# Sheet1.net
KiCad netlist of a schematic drawn in Altium Designer
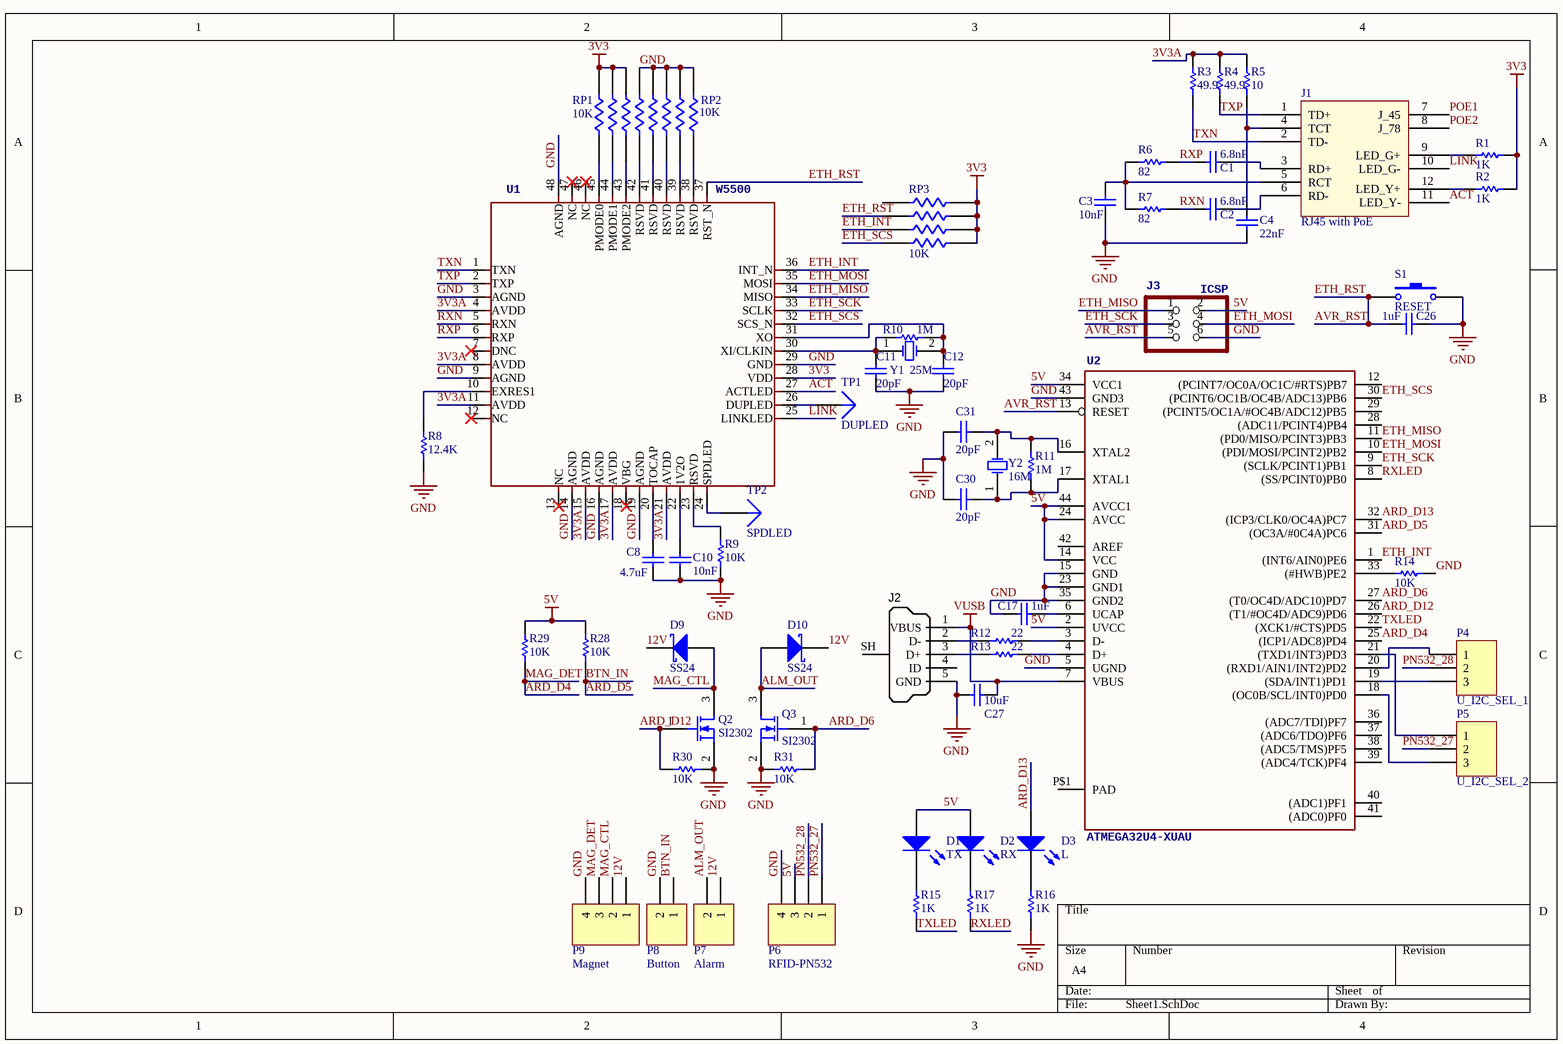
[diagram p0: Sheet1.SchDoc]

(export (version "E")
  (design (tool "Eeschema 10.0.6"))
  (components
    (comp (ref "C1")
      (value "6.8nF")
      (footprint "C-1608[0603]")
      (description "Capacitor (Semiconductor SIM Model)")
      (fields (field (name "Comment") "Cap Semi") (field (name "PUBLISHER") "Altium Limited"))
      (libsource (lib "Miscellaneous Devices") (part "Cap Semi"))
    )
    (comp (ref "C2")
      (value "6.8nF")
      (footprint "C-1608[0603]")
      (description "Capacitor (Semiconductor SIM Model)")
      (fields (field (name "Comment") "Cap Semi") (field (name "PUBLISHER") "Altium Limited"))
      (libsource (lib "Miscellaneous Devices") (part "Cap Semi"))
    )
    (comp (ref "C3")
      (value "10nF")
      (footprint "C-1608[0603]")
      (description "Capacitor (Semiconductor SIM Model)")
      (fields (field (name "Comment") "Cap Semi") (field (name "PUBLISHER") "Altium Limited"))
      (libsource (lib "Miscellaneous Devices") (part "Cap Semi"))
    )
    (comp (ref "C4")
      (value "22nF")
      (footprint "C-1608[0603]")
      (description "Capacitor (Semiconductor SIM Model)")
      (fields (field (name "Comment") "Cap Semi") (field (name "PUBLISHER") "Altium Limited"))
      (libsource (lib "Miscellaneous Devices") (part "Cap Semi"))
    )
    (comp (ref "C8")
      (value "4.7uF")
      (footprint "C-1608[0603]")
      (description "Capacitor (Semiconductor SIM Model)")
      (fields (field (name "Comment") "Cap Semi") (field (name "PUBLISHER") "Altium Limited"))
      (libsource (lib "Miscellaneous Devices") (part "Cap Semi"))
    )
    (comp (ref "C10")
      (value "10nF")
      (footprint "C-1608[0603]")
      (description "Capacitor (Semiconductor SIM Model)")
      (fields (field (name "Comment") "Cap Semi") (field (name "PUBLISHER") "Altium Limited"))
      (libsource (lib "Miscellaneous Devices") (part "Cap Semi"))
    )
    (comp (ref "C11")
      (value "20pF")
      (footprint "C-1608[0603]")
      (description "Capacitor (Semiconductor SIM Model)")
      (fields (field (name "Comment") "Cap Semi") (field (name "PUBLISHER") "Altium Limited"))
      (libsource (lib "Miscellaneous Devices") (part "Cap Semi"))
    )
    (comp (ref "C12")
      (value "20pF")
      (footprint "C-1608[0603]")
      (description "Capacitor (Semiconductor SIM Model)")
      (fields (field (name "Comment") "Cap Semi") (field (name "PUBLISHER") "Altium Limited"))
      (libsource (lib "Miscellaneous Devices") (part "Cap Semi"))
    )
    (comp (ref "C17")
      (value "1uF")
      (footprint "C-1608[0603]")
      (description "Capacitor (Semiconductor SIM Model)")
      (fields (field (name "Comment") "Cap Semi") (field (name "PUBLISHER") "Altium Limited"))
      (libsource (lib "Miscellaneous Devices") (part "Cap Semi"))
    )
    (comp (ref "C26")
      (value "1uF")
      (footprint "C-1608[0603]")
      (description "Capacitor (Semiconductor SIM Model)")
      (fields (field (name "Comment") "Cap Semi") (field (name "PUBLISHER") "Altium Limited"))
      (libsource (lib "Miscellaneous Devices") (part "Cap Semi"))
    )
    (comp (ref "C27")
      (value "10uF")
      (footprint "C-1608[0603]")
      (description "Capacitor (Semiconductor SIM Model)")
      (fields (field (name "Comment") "Cap Semi") (field (name "PUBLISHER") "Altium Limited"))
      (libsource (lib "Miscellaneous Devices") (part "Cap Semi"))
    )
    (comp (ref "C30")
      (value "20pF")
      (footprint "C-1608[0603]")
      (description "Capacitor (Semiconductor SIM Model)")
      (fields (field (name "Comment") "Cap Semi") (field (name "PUBLISHER") "Altium Limited"))
      (libsource (lib "Miscellaneous Devices") (part "Cap Semi"))
    )
    (comp (ref "C31")
      (value "20pF")
      (footprint "C-1608[0603]")
      (description "Capacitor (Semiconductor SIM Model)")
      (fields (field (name "Comment") "Cap Semi") (field (name "PUBLISHER") "Altium Limited"))
      (libsource (lib "Miscellaneous Devices") (part "Cap Semi"))
    )
    (comp (ref "D1")
      (value "TX")
      (footprint "LED-1608[0603]-R")
      (description "Typical RED GaAs LED")
      (fields (field (name "PUBLISHER") "Altium Limited"))
      (libsource (lib "Miscellaneous Devices") (part "LED1"))
    )
    (comp (ref "D2")
      (value "RX")
      (footprint "LED-1608[0603]-R")
      (description "Typical RED GaAs LED")
      (fields (field (name "PUBLISHER") "Altium Limited"))
      (libsource (lib "Miscellaneous Devices") (part "LED1"))
    )
    (comp (ref "D3")
      (value "L")
      (footprint "LED-1608[0603]-R")
      (description "Typical RED GaAs LED")
      (fields (field (name "PUBLISHER") "Altium Limited"))
      (libsource (lib "Miscellaneous Devices") (part "LED1"))
    )
    (comp (ref "D9")
      (value "SS24")
      (footprint "DO-214AC")
      (description "Schottky Diode")
      (fields (field (name "PUBLISHER") "Altium Limited"))
      (libsource (lib "Miscellaneous Devices") (part "D Schottky"))
    )
    (comp (ref "D10")
      (value "SS24")
      (footprint "DO-214AC")
      (description "Schottky Diode")
      (fields (field (name "PUBLISHER") "Altium Limited"))
      (libsource (lib "Miscellaneous Devices") (part "D Schottky"))
    )
    (comp (ref "J1")
      (value "RJ45 with PoE")
      (footprint "HR911105A")
      (libsource (lib "Schlib1") (part "HLJ-6115ANL"))
    )
    (comp (ref "J2")
      (value "USB Micro Type B")
      (footprint "MICRO USB 3D")
      (description "Connector SMD USB Micro Type B middle mount")
      (libsource (lib "Schlib1") (part "USB_Micro_TypeB"))
    )
    (comp (ref "J3") (value "ICSP") (footprint "HDR2X3") (libsource (lib "SmartPrj") (part "PINHD-2X3")))
    (comp (ref "P4")
      (value "U_I2C_SEL_1")
      (footprint "shortPad")
      (description "Header, 3-Pin")
      (fields (field (name "PUBLISHER") "Altium Limited"))
      (libsource (lib "Miscellaneous Connectors") (part "Header 3"))
    )
    (comp (ref "P5")
      (value "U_I2C_SEL_2")
      (footprint "shortPad")
      (description "Header, 3-Pin")
      (fields (field (name "PUBLISHER") "Altium Limited"))
      (libsource (lib "Miscellaneous Connectors") (part "Header 3"))
    )
    (comp (ref "P6")
      (value "RFID-PN532")
      (footprint "HDR1X4H")
      (description "Header, 4-Pin, Right Angle")
      (fields (field (name "PUBLISHER") "Altium Limited"))
      (libsource (lib "Miscellaneous Connectors") (part "Header 4H"))
    )
    (comp (ref "P7")
      (value "Alarm")
      (footprint "HDR1X2H")
      (description "Header, 2-Pin, Right Angle")
      (fields (field (name "PUBLISHER") "Altium Limited"))
      (libsource (lib "Miscellaneous Connectors") (part "Header 2H"))
    )
    (comp (ref "P8")
      (value "Button")
      (footprint "HDR1X2H")
      (description "Header, 2-Pin, Right Angle")
      (fields (field (name "PUBLISHER") "Altium Limited"))
      (libsource (lib "Miscellaneous Connectors") (part "Header 2H"))
    )
    (comp (ref "P9")
      (value "Magnet")
      (footprint "HDR1X4H")
      (description "Header, 4-Pin, Right Angle")
      (fields (field (name "PUBLISHER") "Altium Limited"))
      (libsource (lib "Miscellaneous Connectors") (part "Header 4H"))
    )
    (comp (ref "Q2")
      (value "SI2302")
      (footprint "SOT23B")
      (description "N-Channel MOSFET")
      (fields (field (name "PUBLISHER") "Altium Limited"))
      (libsource (lib "Schlib1") (part "SI2302"))
    )
    (comp (ref "Q3")
      (value "SI2302")
      (footprint "SOT23B")
      (description "N-Channel MOSFET")
      (fields (field (name "PUBLISHER") "Altium Limited"))
      (libsource (lib "Schlib1") (part "SI2302"))
    )
    (comp (ref "R1")
      (value "1K")
      (footprint "R-1608[0603]")
      (description "Semiconductor Resistor")
      (fields (field (name "Comment") "Res Semi") (field (name "PUBLISHER") "Altium Limited"))
      (libsource (lib "Miscellaneous Devices") (part "Res Semi"))
    )
    (comp (ref "R2")
      (value "1K")
      (footprint "R-1608[0603]")
      (description "Semiconductor Resistor")
      (fields (field (name "Comment") "Res Semi") (field (name "PUBLISHER") "Altium Limited"))
      (libsource (lib "Miscellaneous Devices") (part "Res Semi"))
    )
    (comp (ref "R3")
      (value "49.9")
      (footprint "R-1608[0603]")
      (description "Semiconductor Resistor")
      (fields (field (name "Comment") "Res Semi") (field (name "PUBLISHER") "Altium Limited"))
      (libsource (lib "Miscellaneous Devices") (part "Res Semi"))
    )
    (comp (ref "R4")
      (value "49.9")
      (footprint "R-1608[0603]")
      (description "Semiconductor Resistor")
      (fields (field (name "Comment") "Res Semi") (field (name "PUBLISHER") "Altium Limited"))
      (libsource (lib "Miscellaneous Devices") (part "Res Semi"))
    )
    (comp (ref "R5")
      (value "10")
      (footprint "R-1608[0603]")
      (description "Semiconductor Resistor")
      (fields (field (name "Comment") "Res Semi") (field (name "PUBLISHER") "Altium Limited"))
      (libsource (lib "Miscellaneous Devices") (part "Res Semi"))
    )
    (comp (ref "R6")
      (value "82")
      (footprint "R-1608[0603]")
      (description "Semiconductor Resistor")
      (fields (field (name "Comment") "Res Semi") (field (name "PUBLISHER") "Altium Limited"))
      (libsource (lib "Miscellaneous Devices") (part "Res Semi"))
    )
    (comp (ref "R7")
      (value "82")
      (footprint "R-1608[0603]")
      (description "Semiconductor Resistor")
      (fields (field (name "Comment") "Res Semi") (field (name "PUBLISHER") "Altium Limited"))
      (libsource (lib "Miscellaneous Devices") (part "Res Semi"))
    )
    (comp (ref "R8")
      (value "12.4K")
      (footprint "R-1608[0603]")
      (description "Semiconductor Resistor")
      (fields (field (name "Comment") "Res Semi") (field (name "PUBLISHER") "Altium Limited"))
      (libsource (lib "Miscellaneous Devices") (part "Res Semi"))
    )
    (comp (ref "R9")
      (value "10K")
      (footprint "R-1608[0603]")
      (description "Semiconductor Resistor")
      (fields (field (name "Comment") "Res Semi") (field (name "PUBLISHER") "Altium Limited"))
      (libsource (lib "Miscellaneous Devices") (part "Res Semi"))
    )
    (comp (ref "R10")
      (value "1M")
      (footprint "R-1608[0603]")
      (description "Semiconductor Resistor")
      (fields (field (name "Comment") "Res Semi") (field (name "PUBLISHER") "Altium Limited"))
      (libsource (lib "Miscellaneous Devices") (part "Res Semi"))
    )
    (comp (ref "R11")
      (value "1M")
      (footprint "R-1608[0603]")
      (description "Semiconductor Resistor")
      (fields (field (name "Comment") "Res Semi") (field (name "PUBLISHER") "Altium Limited"))
      (libsource (lib "Miscellaneous Devices") (part "Res Semi"))
    )
    (comp (ref "R12")
      (value "22")
      (footprint "R-1608[0603]")
      (description "Semiconductor Resistor")
      (fields (field (name "Comment") "Res Semi") (field (name "PUBLISHER") "Altium Limited"))
      (libsource (lib "Miscellaneous Devices") (part "Res Semi"))
    )
    (comp (ref "R13")
      (value "22")
      (footprint "R-1608[0603]")
      (description "Semiconductor Resistor")
      (fields (field (name "Comment") "Res Semi") (field (name "PUBLISHER") "Altium Limited"))
      (libsource (lib "Miscellaneous Devices") (part "Res Semi"))
    )
    (comp (ref "R14")
      (value "10K")
      (footprint "R-1608[0603]")
      (description "Semiconductor Resistor")
      (fields (field (name "Comment") "Res Semi") (field (name "PUBLISHER") "Altium Limited"))
      (libsource (lib "Miscellaneous Devices") (part "Res Semi"))
    )
    (comp (ref "R15")
      (value "1K")
      (footprint "R-1608[0603]")
      (description "Semiconductor Resistor")
      (fields (field (name "Comment") "Res Semi") (field (name "PUBLISHER") "Altium Limited"))
      (libsource (lib "Miscellaneous Devices") (part "Res Semi"))
    )
    (comp (ref "R16")
      (value "1K")
      (footprint "R-1608[0603]")
      (description "Semiconductor Resistor")
      (fields (field (name "Comment") "Res Semi") (field (name "PUBLISHER") "Altium Limited"))
      (libsource (lib "Miscellaneous Devices") (part "Res Semi"))
    )
    (comp (ref "R17")
      (value "1K")
      (footprint "R-1608[0603]")
      (description "Semiconductor Resistor")
      (fields (field (name "Comment") "Res Semi") (field (name "PUBLISHER") "Altium Limited"))
      (libsource (lib "Miscellaneous Devices") (part "Res Semi"))
    )
    (comp (ref "R28")
      (value "10K")
      (footprint "R-1608[0603]")
      (description "Semiconductor Resistor")
      (fields (field (name "Comment") "Res Semi") (field (name "PUBLISHER") "Altium Limited"))
      (libsource (lib "Miscellaneous Devices") (part "Res Semi"))
    )
    (comp (ref "R29")
      (value "10K")
      (footprint "R-1608[0603]")
      (description "Semiconductor Resistor")
      (fields (field (name "Comment") "Res Semi") (field (name "PUBLISHER") "Altium Limited"))
      (libsource (lib "Miscellaneous Devices") (part "Res Semi"))
    )
    (comp (ref "R30")
      (value "10K")
      (footprint "R-1608[0603]")
      (description "Semiconductor Resistor")
      (fields (field (name "Comment") "Res Semi") (field (name "PUBLISHER") "Altium Limited"))
      (libsource (lib "Miscellaneous Devices") (part "Res Semi"))
    )
    (comp (ref "R31")
      (value "10K")
      (footprint "R-1608[0603]")
      (description "Semiconductor Resistor")
      (fields (field (name "Comment") "Res Semi") (field (name "PUBLISHER") "Altium Limited"))
      (libsource (lib "Miscellaneous Devices") (part "Res Semi"))
    )
    (comp (ref "RP1") (value "10K") (footprint "EXB28V") (libsource (lib "Schlib1") (part "RPACK4")))
    (comp (ref "RP2") (value "10K") (footprint "EXB28V") (libsource (lib "Schlib1") (part "RPACK4")))
    (comp (ref "RP3") (value "10K") (footprint "EXB28V") (libsource (lib "Schlib1") (part "RPACK4")))
    (comp (ref "S1")
      (value "RESET")
      (footprint "SW-2pin-SMD")
      (description "Switch")
      (fields (field (name "PUBLISHER") "Altium Limited"))
      (libsource (lib "Miscellaneous Devices") (part "SW-PB"))
    )
    (comp (ref "TP1")
      (value "DUPLED")
      (footprint "TESTPOINT")
      (description "Plug")
      (fields (field (name "PUBLISHER") "Altium Limited"))
      (libsource (lib "Miscellaneous Connectors") (part "Plug"))
    )
    (comp (ref "TP2")
      (value "SPDLED")
      (footprint "TESTPOINT")
      (description "Plug")
      (fields (field (name "PUBLISHER") "Altium Limited"))
      (libsource (lib "Miscellaneous Connectors") (part "Plug"))
    )
    (comp (ref "U1")
      (value "W5500")
      (footprint "TQFP48_N")
      (libsource (lib "template") (part "DRIVER-W5500"))
    )
    (comp (ref "U2")
      (value "ATMEGA32U4-XUAU")
      (footprint "44A_L")
      (libsource (lib "SmartPrj") (part "ATMEGA32U4-XUAU"))
    )
    (comp (ref "Y1")
      (value "25M")
      (footprint "BCY-W2/D2.1")
      (description "Crystal Oscillator")
      (fields (field (name "PUBLISHER") "Altium Limited"))
      (libsource (lib "Miscellaneous Devices") (part "XTAL"))
    )
    (comp (ref "Y2")
      (value "16M")
      (footprint "BCY-W2/D2.1")
      (description "Crystal Oscillator")
      (fields (field (name "PUBLISHER") "Altium Limited"))
      (libsource (lib "Miscellaneous Devices") (part "XTAL"))
    )
  )
  (nets
    (net (code "1") (name "/3V3A") (class "Default")
      (node (ref "R3") (pin "2") (pinfunction "2_2") (pintype "passive"))
      (node (ref "R4") (pin "2") (pinfunction "2_2") (pintype "passive"))
      (node (ref "R5") (pin "2") (pinfunction "2_2") (pintype "passive"))
      (node (ref "U1") (pin "11") (pinfunction "AVDD_11") (pintype "passive"))
      (node (ref "U1") (pin "15") (pinfunction "AVDD_15") (pintype "passive"))
      (node (ref "U1") (pin "17") (pinfunction "AVDD_17") (pintype "passive"))
      (node (ref "U1") (pin "21") (pinfunction "AVDD_21") (pintype "passive"))
      (node (ref "U1") (pin "4") (pinfunction "AVDD_4") (pintype "passive"))
      (node (ref "U1") (pin "8") (pinfunction "AVDD_8") (pintype "passive"))
    )
    (net (code "2") (name "/12V") (class "Default")
      (node (ref "D10") (pin "2") (pinfunction "K_2") (pintype "passive"))
      (node (ref "D9") (pin "2") (pinfunction "K_2") (pintype "passive"))
      (node (ref "P7") (pin "1") (pinfunction "1_1") (pintype "passive"))
      (node (ref "P9") (pin "1") (pinfunction "1_1") (pintype "passive"))
    )
    (net (code "3") (name "/ACT") (class "Default")
      (node (ref "J1") (pin "11") (pinfunction "LED_Y-_11") (pintype "passive"))
      (node (ref "U1") (pin "27") (pinfunction "ACTLED_27") (pintype "passive"))
    )
    (net (code "4") (name "/ALM_OUT") (class "Default")
      (node (ref "D10") (pin "1") (pinfunction "A_1") (pintype "passive"))
      (node (ref "P7") (pin "2") (pinfunction "2_2") (pintype "passive"))
      (node (ref "Q3") (pin "3") (pinfunction "D_3") (pintype "passive"))
    )
    (net (code "5") (name "/ARD_D4") (class "Default")
      (node (ref "P9") (pin "3") (pinfunction "3_3") (pintype "passive"))
      (node (ref "R29") (pin "1") (pinfunction "1_1") (pintype "passive"))
      (node (ref "U2") (pin "25") (pinfunction "(ICP1/ADC8)PD4_25") (pintype "passive"))
    )
    (net (code "6") (name "/ARD_D5") (class "Default")
      (node (ref "P8") (pin "1") (pinfunction "1_1") (pintype "passive"))
      (node (ref "R28") (pin "1") (pinfunction "1_1") (pintype "passive"))
      (node (ref "U2") (pin "31") (pinfunction "(OC3A/#0C4A)PC6_31") (pintype "passive"))
    )
    (net (code "7") (name "/ARD_D6") (class "Default")
      (node (ref "Q3") (pin "1") (pinfunction "G_1") (pintype "passive"))
      (node (ref "R31") (pin "1") (pinfunction "1_1") (pintype "passive"))
      (node (ref "U2") (pin "27") (pinfunction "(T0/OC4D/ADC10)PD7_27") (pintype "passive"))
    )
    (net (code "8") (name "/ARD_D12") (class "Default")
      (node (ref "Q2") (pin "1") (pinfunction "G_1") (pintype "passive"))
      (node (ref "R30") (pin "2") (pinfunction "2_2") (pintype "passive"))
      (node (ref "U2") (pin "26") (pinfunction "(T1/#OC4D/ADC9)PD6_26") (pintype "passive"))
    )
    (net (code "9") (name "/ARD_D13") (class "Default")
      (node (ref "D3") (pin "1") (pinfunction "A_1") (pintype "passive"))
      (node (ref "U2") (pin "32") (pinfunction "(ICP3/CLK0/OC4A)PC7_32") (pintype "passive"))
    )
    (net (code "10") (name "/AVR_RST") (class "Default")
      (node (ref "C26") (pin "1") (pinfunction "1_1") (pintype "passive"))
      (node (ref "J3") (pin "5") (pinfunction "5_5") (pintype "passive"))
      (node (ref "RP3") (pin "6") (pinfunction "6_6") (pintype "passive"))
      (node (ref "S1") (pin "1") (pinfunction "1_1") (pintype "passive"))
      (node (ref "U1") (pin "37") (pinfunction "RST_N_37") (pintype "passive"))
      (node (ref "U2") (pin "13") (pinfunction "RESET_13") (pintype "passive"))
    )
    (net (code "11") (name "/ETH_INT") (class "Default")
      (node (ref "RP3") (pin "7") (pinfunction "7_7") (pintype "passive"))
      (node (ref "U1") (pin "36") (pinfunction "INT_N_36") (pintype "passive"))
      (node (ref "U2") (pin "1") (pinfunction "(INT6/AIN0)PE6_1") (pintype "passive"))
    )
    (net (code "12") (name "/ETH_MISO") (class "Default")
      (node (ref "J3") (pin "1") (pinfunction "1_1") (pintype "passive"))
      (node (ref "U1") (pin "34") (pinfunction "MISO_34") (pintype "passive"))
      (node (ref "U2") (pin "11") (pinfunction "(PD0/MISO/PCINT3)PB3_11") (pintype "passive"))
    )
    (net (code "13") (name "/ETH_MOSI") (class "Default")
      (node (ref "J3") (pin "4") (pinfunction "4_4") (pintype "passive"))
      (node (ref "U1") (pin "35") (pinfunction "MOSI_35") (pintype "passive"))
      (node (ref "U2") (pin "10") (pinfunction "(PDI/MOSI/PCINT2)PB2_10") (pintype "passive"))
    )
    (net (code "14") (name "/ETH_SCK") (class "Default")
      (node (ref "J3") (pin "3") (pinfunction "3_3") (pintype "passive"))
      (node (ref "U1") (pin "33") (pinfunction "SCLK_33") (pintype "passive"))
      (node (ref "U2") (pin "9") (pinfunction "(SCLK/PCINT1)PB1_9") (pintype "passive"))
    )
    (net (code "15") (name "/ETH_SCS") (class "Default")
      (node (ref "RP3") (pin "8") (pinfunction "8_8") (pintype "passive"))
      (node (ref "U1") (pin "32") (pinfunction "SCS_N_32") (pintype "passive"))
      (node (ref "U2") (pin "30") (pinfunction "(PCINT6/OC1B/OC4B/ADC13)PB6_30") (pintype "passive"))
    )
    (net (code "16") (name "/LINK") (class "Default")
      (node (ref "J1") (pin "10") (pinfunction "LED_G-_10") (pintype "passive"))
      (node (ref "U1") (pin "25") (pinfunction "LINKLED_25") (pintype "passive"))
    )
    (net (code "17") (name "/MAG_CTL") (class "Default")
      (node (ref "D9") (pin "1") (pinfunction "A_1") (pintype "passive"))
      (node (ref "P9") (pin "2") (pinfunction "2_2") (pintype "passive"))
      (node (ref "Q2") (pin "3") (pinfunction "D_3") (pintype "passive"))
    )
    (net (code "18") (name "/PN532_27") (class "Default")
      (node (ref "P5") (pin "2") (pinfunction "2_2") (pintype "passive"))
      (node (ref "P6") (pin "1") (pinfunction "1_1") (pintype "passive"))
    )
    (net (code "19") (name "/PN532_28") (class "Default")
      (node (ref "P4") (pin "2") (pinfunction "2_2") (pintype "passive"))
      (node (ref "P6") (pin "2") (pinfunction "2_2") (pintype "passive"))
    )
    (net (code "20") (name "/POE1") (class "Default")
      (node (ref "J1") (pin "7") (pinfunction "J_45_7") (pintype "passive"))
    )
    (net (code "21") (name "/POE2") (class "Default")
      (node (ref "J1") (pin "8") (pinfunction "J_78_8") (pintype "passive"))
    )
    (net (code "22") (name "/RXLED") (class "Default")
      (node (ref "R17") (pin "1") (pinfunction "1_1") (pintype "passive"))
      (node (ref "U2") (pin "8") (pinfunction "(SS/PCINT0)PB0_8") (pintype "passive"))
    )
    (net (code "23") (name "/RXN") (class "Default")
      (node (ref "C2") (pin "1") (pinfunction "1_1") (pintype "passive"))
      (node (ref "R7") (pin "1") (pinfunction "1_1") (pintype "passive"))
      (node (ref "U1") (pin "5") (pinfunction "RXN_5") (pintype "passive"))
    )
    (net (code "24") (name "/RXP") (class "Default")
      (node (ref "C1") (pin "1") (pinfunction "1_1") (pintype "passive"))
      (node (ref "R6") (pin "1") (pinfunction "1_1") (pintype "passive"))
      (node (ref "U1") (pin "6") (pinfunction "RXP_6") (pintype "passive"))
    )
    (net (code "25") (name "/TXLED") (class "Default")
      (node (ref "R15") (pin "1") (pinfunction "1_1") (pintype "passive"))
      (node (ref "U2") (pin "22") (pinfunction "(XCK1/#CTS)PD5_22") (pintype "passive"))
    )
    (net (code "26") (name "/TXN") (class "Default")
      (node (ref "J1") (pin "2") (pinfunction "TD-_2") (pintype "passive"))
      (node (ref "R3") (pin "1") (pinfunction "1_1") (pintype "passive"))
      (node (ref "U1") (pin "1") (pinfunction "TXN_1") (pintype "passive"))
    )
    (net (code "27") (name "/TXP") (class "Default")
      (node (ref "J1") (pin "1") (pinfunction "TD+_1") (pintype "passive"))
      (node (ref "R4") (pin "1") (pinfunction "1_1") (pintype "passive"))
      (node (ref "U1") (pin "2") (pinfunction "TXP_2") (pintype "passive"))
    )
    (net (code "28") (name "3V3") (class "Default")
      (node (ref "R1") (pin "2") (pinfunction "2_2") (pintype "passive"))
      (node (ref "R2") (pin "2") (pinfunction "2_2") (pintype "passive"))
      (node (ref "RP1") (pin "6") (pinfunction "6_6") (pintype "passive"))
      (node (ref "RP1") (pin "7") (pinfunction "7_7") (pintype "passive"))
      (node (ref "RP1") (pin "8") (pinfunction "8_8") (pintype "passive"))
      (node (ref "RP3") (pin "1") (pinfunction "1_1") (pintype "passive"))
      (node (ref "RP3") (pin "2") (pinfunction "2_2") (pintype "passive"))
      (node (ref "RP3") (pin "3") (pinfunction "3_3") (pintype "passive"))
      (node (ref "RP3") (pin "4") (pinfunction "4_4") (pintype "passive"))
      (node (ref "U1") (pin "28") (pinfunction "VDD_28") (pintype "passive"))
    )
    (net (code "29") (name "5V") (class "Default")
      (node (ref "D1") (pin "1") (pinfunction "A_1") (pintype "passive"))
      (node (ref "D2") (pin "1") (pinfunction "A_1") (pintype "passive"))
      (node (ref "J3") (pin "2") (pinfunction "2_2") (pintype "passive"))
      (node (ref "P6") (pin "3") (pinfunction "3_3") (pintype "passive"))
      (node (ref "R28") (pin "2") (pinfunction "2_2") (pintype "passive"))
      (node (ref "R29") (pin "2") (pinfunction "2_2") (pintype "passive"))
      (node (ref "U2") (pin "14") (pinfunction "VCC_14") (pintype "power_in"))
      (node (ref "U2") (pin "2") (pinfunction "UVCC_2") (pintype "power_in"))
      (node (ref "U2") (pin "24") (pinfunction "AVCC_24") (pintype "power_in"))
      (node (ref "U2") (pin "34") (pinfunction "VCC1_34") (pintype "power_in"))
      (node (ref "U2") (pin "44") (pinfunction "AVCC1_44") (pintype "power_in"))
    )
    (net (code "30") (name "GND") (class "Default")
      (node (ref "C10") (pin "1") (pinfunction "1_1") (pintype "passive"))
      (node (ref "C11") (pin "1") (pinfunction "1_1") (pintype "passive"))
      (node (ref "C12") (pin "1") (pinfunction "1_1") (pintype "passive"))
      (node (ref "C17") (pin "1") (pinfunction "1_1") (pintype "passive"))
      (node (ref "C26") (pin "2") (pinfunction "2_2") (pintype "passive"))
      (node (ref "C27") (pin "2") (pinfunction "2_2") (pintype "passive"))
      (node (ref "C3") (pin "2") (pinfunction "2_2") (pintype "passive"))
      (node (ref "C30") (pin "2") (pinfunction "2_2") (pintype "passive"))
      (node (ref "C31") (pin "2") (pinfunction "2_2") (pintype "passive"))
      (node (ref "C4") (pin "1") (pinfunction "1_1") (pintype "passive"))
      (node (ref "C8") (pin "1") (pinfunction "1_1") (pintype "passive"))
      (node (ref "J2") (pin "5") (pinfunction "GND_5") (pintype "passive"))
      (node (ref "J3") (pin "6") (pinfunction "6_6") (pintype "passive"))
      (node (ref "P6") (pin "4") (pinfunction "4_4") (pintype "passive"))
      (node (ref "P8") (pin "2") (pinfunction "2_2") (pintype "passive"))
      (node (ref "P9") (pin "4") (pinfunction "4_4") (pintype "passive"))
      (node (ref "Q2") (pin "2") (pinfunction "S_2") (pintype "passive"))
      (node (ref "Q3") (pin "2") (pinfunction "S_2") (pintype "passive"))
      (node (ref "R14") (pin "1") (pinfunction "1_1") (pintype "passive"))
      (node (ref "R16") (pin "1") (pinfunction "1_1") (pintype "passive"))
      (node (ref "R30") (pin "1") (pinfunction "1_1") (pintype "passive"))
      (node (ref "R31") (pin "2") (pinfunction "2_2") (pintype "passive"))
      (node (ref "R8") (pin "1") (pinfunction "1_1") (pintype "passive"))
      (node (ref "R9") (pin "1") (pinfunction "1_1") (pintype "passive"))
      (node (ref "RP1") (pin "5") (pinfunction "5_5") (pintype "passive"))
      (node (ref "RP2") (pin "5") (pinfunction "5_5") (pintype "passive"))
      (node (ref "RP2") (pin "6") (pinfunction "6_6") (pintype "passive"))
      (node (ref "RP2") (pin "7") (pinfunction "7_7") (pintype "passive"))
      (node (ref "RP2") (pin "8") (pinfunction "8_8") (pintype "passive"))
      (node (ref "S1") (pin "2") (pinfunction "2_2") (pintype "passive"))
      (node (ref "U1") (pin "14") (pinfunction "AGND_14") (pintype "passive"))
      (node (ref "U1") (pin "16") (pinfunction "AGND_16") (pintype "passive"))
      (node (ref "U1") (pin "19") (pinfunction "AGND_19") (pintype "passive"))
      (node (ref "U1") (pin "29") (pinfunction "GND_29") (pintype "passive"))
      (node (ref "U1") (pin "3") (pinfunction "AGND_3") (pintype "passive"))
      (node (ref "U1") (pin "48") (pinfunction "AGND_48") (pintype "passive"))
      (node (ref "U1") (pin "9") (pinfunction "AGND_9") (pintype "passive"))
      (node (ref "U2") (pin "15") (pinfunction "GND_15") (pintype "power_in"))
      (node (ref "U2") (pin "23") (pinfunction "GND1_23") (pintype "power_in"))
      (node (ref "U2") (pin "35") (pinfunction "GND2_35") (pintype "power_in"))
      (node (ref "U2") (pin "43") (pinfunction "GND3_43") (pintype "power_in"))
      (node (ref "U2") (pin "5") (pinfunction "UGND_5") (pintype "power_in"))
    )
    (net (code "31") (name "Net-(D1-K)") (class "Default")
      (node (ref "D1") (pin "2") (pinfunction "K_2") (pintype "passive"))
      (node (ref "R15") (pin "2") (pinfunction "2_2") (pintype "passive"))
    )
    (net (code "32") (name "Net-(D2-K)") (class "Default")
      (node (ref "D2") (pin "2") (pinfunction "K_2") (pintype "passive"))
      (node (ref "R17") (pin "2") (pinfunction "2_2") (pintype "passive"))
    )
    (net (code "33") (name "Net-(D3-K)") (class "Default")
      (node (ref "D3") (pin "2") (pinfunction "K_2") (pintype "passive"))
      (node (ref "R16") (pin "2") (pinfunction "2_2") (pintype "passive"))
    )
    (net (code "34") (name "Net-(J1-LED_G+)") (class "Default")
      (node (ref "J1") (pin "9") (pinfunction "LED_G+_9") (pintype "passive"))
      (node (ref "R1") (pin "1") (pinfunction "1_1") (pintype "passive"))
    )
    (net (code "35") (name "Net-(J1-LED_Y+)") (class "Default")
      (node (ref "J1") (pin "12") (pinfunction "LED_Y+_12") (pintype "passive"))
      (node (ref "R2") (pin "1") (pinfunction "1_1") (pintype "passive"))
    )
    (net (code "36") (name "Net-(J1-RCT)") (class "Default")
      (node (ref "C3") (pin "1") (pinfunction "1_1") (pintype "passive"))
      (node (ref "J1") (pin "5") (pinfunction "RCT_5") (pintype "passive"))
      (node (ref "R6") (pin "2") (pinfunction "2_2") (pintype "passive"))
      (node (ref "R7") (pin "2") (pinfunction "2_2") (pintype "passive"))
    )
    (net (code "37") (name "Net-(J1-RD+)") (class "Default")
      (node (ref "C1") (pin "2") (pinfunction "2_2") (pintype "passive"))
      (node (ref "J1") (pin "3") (pinfunction "RD+_3") (pintype "passive"))
    )
    (net (code "38") (name "Net-(J1-RD-)") (class "Default")
      (node (ref "C2") (pin "2") (pinfunction "2_2") (pintype "passive"))
      (node (ref "J1") (pin "6") (pinfunction "RD-_6") (pintype "passive"))
    )
    (net (code "39") (name "Net-(J1-TCT)") (class "Default")
      (node (ref "C4") (pin "2") (pinfunction "2_2") (pintype "passive"))
      (node (ref "J1") (pin "4") (pinfunction "TCT_4") (pintype "passive"))
      (node (ref "R5") (pin "1") (pinfunction "1_1") (pintype "passive"))
    )
    (net (code "40") (name "Net-(J2-D+)") (class "Default")
      (node (ref "J2") (pin "3") (pinfunction "D+_3") (pintype "passive"))
      (node (ref "R13") (pin "2") (pinfunction "2_2") (pintype "passive"))
    )
    (net (code "41") (name "Net-(J2-D-)") (class "Default")
      (node (ref "J2") (pin "2") (pinfunction "D-_2") (pintype "passive"))
      (node (ref "R12") (pin "2") (pinfunction "2_2") (pintype "passive"))
    )
    (net (code "42") (name "Net-(R9-Pad2)") (class "Default")
      (node (ref "R9") (pin "2") (pinfunction "2_2") (pintype "passive"))
      (node (ref "U1") (pin "23") (pinfunction "RSVD_23") (pintype "passive"))
    )
    (net (code "43") (name "Net-(RP1-Pad4)") (class "Default")
      (node (ref "RP1") (pin "4") (pinfunction "4_4") (pintype "passive"))
      (node (ref "U1") (pin "42") (pinfunction "RSVD_42") (pintype "passive"))
    )
    (net (code "44") (name "Net-(RP2-Pad1)") (class "Default")
      (node (ref "RP2") (pin "1") (pinfunction "1_1") (pintype "passive"))
      (node (ref "U1") (pin "41") (pinfunction "RSVD_41") (pintype "passive"))
    )
    (net (code "45") (name "Net-(RP2-Pad2)") (class "Default")
      (node (ref "RP2") (pin "2") (pinfunction "2_2") (pintype "passive"))
      (node (ref "U1") (pin "40") (pinfunction "RSVD_40") (pintype "passive"))
    )
    (net (code "46") (name "Net-(RP2-Pad3)") (class "Default")
      (node (ref "RP2") (pin "3") (pinfunction "3_3") (pintype "passive"))
      (node (ref "U1") (pin "39") (pinfunction "RSVD_39") (pintype "passive"))
    )
    (net (code "47") (name "Net-(RP2-Pad4)") (class "Default")
      (node (ref "RP2") (pin "4") (pinfunction "4_4") (pintype "passive"))
      (node (ref "U1") (pin "38") (pinfunction "RSVD_38") (pintype "passive"))
    )
    (net (code "48") (name "Net-(U1-1V2O)") (class "Default")
      (node (ref "C10") (pin "2") (pinfunction "2_2") (pintype "passive"))
      (node (ref "U1") (pin "22") (pinfunction "1V2O_22") (pintype "passive"))
    )
    (net (code "49") (name "Net-(U1-DUPLED)") (class "Default")
      (node (ref "TP1") (pin "1") (pinfunction "1_1") (pintype "passive"))
      (node (ref "U1") (pin "26") (pinfunction "DUPLED_26") (pintype "passive"))
    )
    (net (code "50") (name "Net-(U1-EXRES1)") (class "Default")
      (node (ref "R8") (pin "2") (pinfunction "2_2") (pintype "passive"))
      (node (ref "U1") (pin "10") (pinfunction "EXRES1_10") (pintype "passive"))
    )
    (net (code "51") (name "Net-(U1-PMODE0)") (class "Default")
      (node (ref "RP1") (pin "1") (pinfunction "1_1") (pintype "passive"))
      (node (ref "U1") (pin "45") (pinfunction "PMODE0_45") (pintype "passive"))
    )
    (net (code "52") (name "Net-(U1-PMODE1)") (class "Default")
      (node (ref "RP1") (pin "2") (pinfunction "2_2") (pintype "passive"))
      (node (ref "U1") (pin "44") (pinfunction "PMODE1_44") (pintype "passive"))
    )
    (net (code "53") (name "Net-(U1-PMODE2)") (class "Default")
      (node (ref "RP1") (pin "3") (pinfunction "3_3") (pintype "passive"))
      (node (ref "U1") (pin "43") (pinfunction "PMODE2_43") (pintype "passive"))
    )
    (net (code "54") (name "Net-(U1-SPDLED)") (class "Default")
      (node (ref "TP2") (pin "1") (pinfunction "1_1") (pintype "passive"))
      (node (ref "U1") (pin "24") (pinfunction "SPDLED_24") (pintype "passive"))
    )
    (net (code "55") (name "Net-(U1-TOCAP)") (class "Default")
      (node (ref "C8") (pin "2") (pinfunction "2_2") (pintype "passive"))
      (node (ref "U1") (pin "20") (pinfunction "TOCAP_20") (pintype "passive"))
    )
    (net (code "56") (name "Net-(U1-XI{slash}CLKIN)") (class "Default")
      (node (ref "C11") (pin "2") (pinfunction "2_2") (pintype "passive"))
      (node (ref "R10") (pin "2") (pinfunction "2_2") (pintype "passive"))
      (node (ref "U1") (pin "30") (pinfunction "XI/CLKIN_30") (pintype "passive"))
      (node (ref "Y1") (pin "1") (pinfunction "OSC1_1") (pintype "passive"))
    )
    (net (code "57") (name "Net-(U1-XO)") (class "Default")
      (node (ref "C12") (pin "2") (pinfunction "2_2") (pintype "passive"))
      (node (ref "R10") (pin "1") (pinfunction "1_1") (pintype "passive"))
      (node (ref "U1") (pin "31") (pinfunction "XO_31") (pintype "passive"))
      (node (ref "Y1") (pin "2") (pinfunction "OSC2_2") (pintype "passive"))
    )
    (net (code "58") (name "Net-(U2-(#HWB)PE2)") (class "Default")
      (node (ref "R14") (pin "2") (pinfunction "2_2") (pintype "passive"))
      (node (ref "U2") (pin "33") (pinfunction "(#HWB)PE2_33") (pintype "passive"))
    )
    (net (code "59") (name "Net-(U2-(OC0B{slash}SCL{slash}INT0)PD0)") (class "Default")
      (node (ref "P5") (pin "3") (pinfunction "3_3") (pintype "passive"))
      (node (ref "U2") (pin "18") (pinfunction "(OC0B/SCL/INT0)PD0_18") (pintype "passive"))
    )
    (net (code "60") (name "Net-(U2-(RXD1{slash}AIN1{slash}INT2)PD2)") (class "Default")
      (node (ref "P4") (pin "1") (pinfunction "1_1") (pintype "passive"))
      (node (ref "U2") (pin "20") (pinfunction "(RXD1/AIN1/INT2)PD2_20") (pintype "passive"))
    )
    (net (code "61") (name "Net-(U2-(SDA{slash}INT1)PD1)") (class "Default")
      (node (ref "P4") (pin "3") (pinfunction "3_3") (pintype "passive"))
      (node (ref "U2") (pin "19") (pinfunction "(SDA/INT1)PD1_19") (pintype "passive"))
    )
    (net (code "62") (name "Net-(U2-(TXD1{slash}INT3)PD3)") (class "Default")
      (node (ref "P5") (pin "1") (pinfunction "1_1") (pintype "passive"))
      (node (ref "U2") (pin "21") (pinfunction "(TXD1/INT3)PD3_21") (pintype "passive"))
    )
    (net (code "63") (name "Net-(U2-D+)") (class "Default")
      (node (ref "R13") (pin "1") (pinfunction "1_1") (pintype "passive"))
      (node (ref "U2") (pin "4") (pinfunction "D+_4") (pintype "passive"))
    )
    (net (code "64") (name "Net-(U2-D-)") (class "Default")
      (node (ref "R12") (pin "1") (pinfunction "1_1") (pintype "passive"))
      (node (ref "U2") (pin "3") (pinfunction "D-_3") (pintype "passive"))
    )
    (net (code "65") (name "Net-(U2-UCAP)") (class "Default")
      (node (ref "C17") (pin "2") (pinfunction "2_2") (pintype "passive"))
      (node (ref "U2") (pin "6") (pinfunction "UCAP_6") (pintype "passive"))
    )
    (net (code "66") (name "Net-(U2-XTAL1)") (class "Default")
      (node (ref "C30") (pin "1") (pinfunction "1_1") (pintype "passive"))
      (node (ref "R11") (pin "2") (pinfunction "2_2") (pintype "passive"))
      (node (ref "U2") (pin "17") (pinfunction "XTAL1_17") (pintype "passive"))
      (node (ref "Y2") (pin "1") (pinfunction "OSC1_1") (pintype "passive"))
    )
    (net (code "67") (name "Net-(U2-XTAL2)") (class "Default")
      (node (ref "C31") (pin "1") (pinfunction "1_1") (pintype "passive"))
      (node (ref "R11") (pin "1") (pinfunction "1_1") (pintype "passive"))
      (node (ref "U2") (pin "16") (pinfunction "XTAL2_16") (pintype "passive"))
      (node (ref "Y2") (pin "2") (pinfunction "OSC2_2") (pintype "passive"))
    )
    (net (code "68") (name "VUSB") (class "Default")
      (node (ref "C27") (pin "1") (pinfunction "1_1") (pintype "passive"))
      (node (ref "J2") (pin "1") (pinfunction "VBUS_1") (pintype "passive"))
      (node (ref "U2") (pin "7") (pinfunction "VBUS_7") (pintype "passive"))
    )
    (net (code "69") (name "unconnected-(J2-ID-Pad4)") (class "Default")
      (node (ref "J2") (pin "4") (pinfunction "ID_4") (pintype "passive"))
    )
    (net (code "70") (name "unconnected-(J2-Shell-PadSH)") (class "Default")
      (node (ref "J2") (pin "SH") (pinfunction "Shell_SH") (pintype "passive"))
    )
    (net (code "71") (name "unconnected-(RP3-Pad5)") (class "Default")
      (node (ref "RP3") (pin "5") (pinfunction "5_5") (pintype "passive"))
    )
    (net (code "72") (name "unconnected-(U1-DNC-Pad7)") (class "Default")
      (node (ref "U1") (pin "7") (pinfunction "DNC_7") (pintype "passive+no_connect"))
    )
    (net (code "73") (name "unconnected-(U1-NC-Pad12)") (class "Default")
      (node (ref "U1") (pin "12") (pinfunction "NC_12") (pintype "passive+no_connect"))
    )
    (net (code "74") (name "unconnected-(U1-NC-Pad13)") (class "Default")
      (node (ref "U1") (pin "13") (pinfunction "NC_13") (pintype "passive+no_connect"))
    )
    (net (code "75") (name "unconnected-(U1-NC-Pad46)") (class "Default")
      (node (ref "U1") (pin "46") (pinfunction "NC_46") (pintype "passive+no_connect"))
    )
    (net (code "76") (name "unconnected-(U1-NC-Pad47)") (class "Default")
      (node (ref "U1") (pin "47") (pinfunction "NC_47") (pintype "passive+no_connect"))
    )
    (net (code "77") (name "unconnected-(U1-VBG-Pad18)") (class "Default")
      (node (ref "U1") (pin "18") (pinfunction "VBG_18") (pintype "passive+no_connect"))
    )
    (net (code "78") (name "unconnected-(U2-(ADC0)PF0-Pad41)") (class "Default")
      (node (ref "U2") (pin "41") (pinfunction "(ADC0)PF0_41") (pintype "passive"))
    )
    (net (code "79") (name "unconnected-(U2-(ADC1)PF1-Pad40)") (class "Default")
      (node (ref "U2") (pin "40") (pinfunction "(ADC1)PF1_40") (pintype "passive"))
    )
    (net (code "80") (name "unconnected-(U2-(ADC4{slash}TCK)PF4-Pad39)") (class "Default")
      (node (ref "U2") (pin "39") (pinfunction "(ADC4/TCK)PF4_39") (pintype "passive"))
    )
    (net (code "81") (name "unconnected-(U2-(ADC5{slash}TMS)PF5-Pad38)") (class "Default")
      (node (ref "U2") (pin "38") (pinfunction "(ADC5/TMS)PF5_38") (pintype "passive"))
    )
    (net (code "82") (name "unconnected-(U2-(ADC6{slash}TDO)PF6-Pad37)") (class "Default")
      (node (ref "U2") (pin "37") (pinfunction "(ADC6/TDO)PF6_37") (pintype "passive"))
    )
    (net (code "83") (name "unconnected-(U2-(ADC7{slash}TDI)PF7-Pad36)") (class "Default")
      (node (ref "U2") (pin "36") (pinfunction "(ADC7/TDI)PF7_36") (pintype "passive"))
    )
    (net (code "84") (name "unconnected-(U2-(ADC11{slash}PCINT4)PB4-Pad28)") (class "Default")
      (node (ref "U2") (pin "28") (pinfunction "(ADC11/PCINT4)PB4_28") (pintype "passive"))
    )
    (net (code "85") (name "unconnected-(U2-(PCINT5{slash}OC1A{slash}#OC4B{slash}ADC12)PB5-Pad29)") (class "Default")
      (node (ref "U2") (pin "29") (pinfunction "(PCINT5/OC1A/#OC4B/ADC12)PB5_29") (pintype "passive"))
    )
    (net (code "86") (name "unconnected-(U2-(PCINT7{slash}OC0A{slash}OC1C{slash}#RTS)PB7-Pad12)") (class "Default")
      (node (ref "U2") (pin "12") (pinfunction "(PCINT7/OC0A/OC1C/#RTS)PB7_12") (pintype "passive"))
    )
    (net (code "87") (name "unconnected-(U2-AREF-Pad42)") (class "Default")
      (node (ref "U2") (pin "42") (pinfunction "AREF_42") (pintype "power_in"))
    )
    (net (code "88") (name "unconnected-(U2-PAD-PadP$1)") (class "Default")
      (node (ref "U2") (pin "P$1") (pinfunction "PAD_P$1") (pintype "power_in"))
    )
  )
)
